# design.net
KiCad netlist of a schematic drawn in Altium Designer
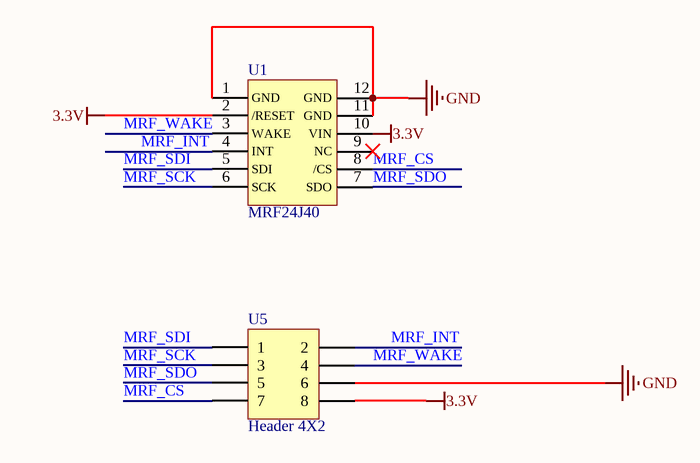
[diagram p0: 覆铜板转接.SchDoc]

(export (version "E")
  (design (tool "Eeschema 10.0.6"))
  (components
    (comp (ref "U1") (value "MRF24J40") (footprint "MRF24J40") (libsource (lib "2号库") (part "MRF24J40")))
    (comp (ref "U5")
      (value "Header 4X2")
      (footprint "HDR2X4")
      (description "Header, 4-Pin, Dual row")
      (fields (field (name "PUBLISHER") "Altium Limited"))
      (libsource (lib "Sparks") (part "Header 4X2"))
    )
  )
  (nets
    (net (code "1") (name "/MRF_CS") (class "Default")
      (node (ref "U1") (pin "8") (pinfunction "/CS_8") (pintype "passive"))
      (node (ref "U5") (pin "7") (pinfunction "7_7") (pintype "passive"))
    )
    (net (code "2") (name "/MRF_INT") (class "Default")
      (node (ref "U1") (pin "4") (pinfunction "INT_4") (pintype "passive"))
      (node (ref "U5") (pin "2") (pinfunction "2_2") (pintype "passive"))
    )
    (net (code "3") (name "/MRF_SCK") (class "Default")
      (node (ref "U1") (pin "6") (pinfunction "SCK_6") (pintype "passive"))
      (node (ref "U5") (pin "3") (pinfunction "3_3") (pintype "passive"))
    )
    (net (code "4") (name "/MRF_SDI") (class "Default")
      (node (ref "U1") (pin "5") (pinfunction "SDI_5") (pintype "passive"))
      (node (ref "U5") (pin "1") (pinfunction "1_1") (pintype "passive"))
    )
    (net (code "5") (name "/MRF_SDO") (class "Default")
      (node (ref "U1") (pin "7") (pinfunction "SDO_7") (pintype "passive"))
      (node (ref "U5") (pin "5") (pinfunction "5_5") (pintype "passive"))
    )
    (net (code "6") (name "/MRF_WAKE") (class "Default")
      (node (ref "U1") (pin "3") (pinfunction "WAKE_3") (pintype "passive"))
      (node (ref "U5") (pin "4") (pinfunction "4_4") (pintype "passive"))
    )
    (net (code "7") (name "3.3V") (class "Default")
      (node (ref "U1") (pin "10") (pinfunction "VIN_10") (pintype "passive"))
      (node (ref "U1") (pin "2") (pinfunction "/RESET_2") (pintype "passive"))
      (node (ref "U5") (pin "8") (pinfunction "8_8") (pintype "passive"))
    )
    (net (code "8") (name "GND") (class "Default")
      (node (ref "U1") (pin "1") (pinfunction "GND_1") (pintype "passive"))
      (node (ref "U1") (pin "11") (pinfunction "GND_11") (pintype "passive"))
      (node (ref "U1") (pin "12") (pinfunction "GND_12") (pintype "passive"))
      (node (ref "U5") (pin "6") (pinfunction "6_6") (pintype "passive"))
    )
    (net (code "9") (name "unconnected-(U1-NC-Pad9)") (class "Default")
      (node (ref "U1") (pin "9") (pinfunction "NC_9") (pintype "passive+no_connect"))
    )
  )
)
